# PWR_SW.net
KiCad netlist of a schematic drawn in Altium Designer
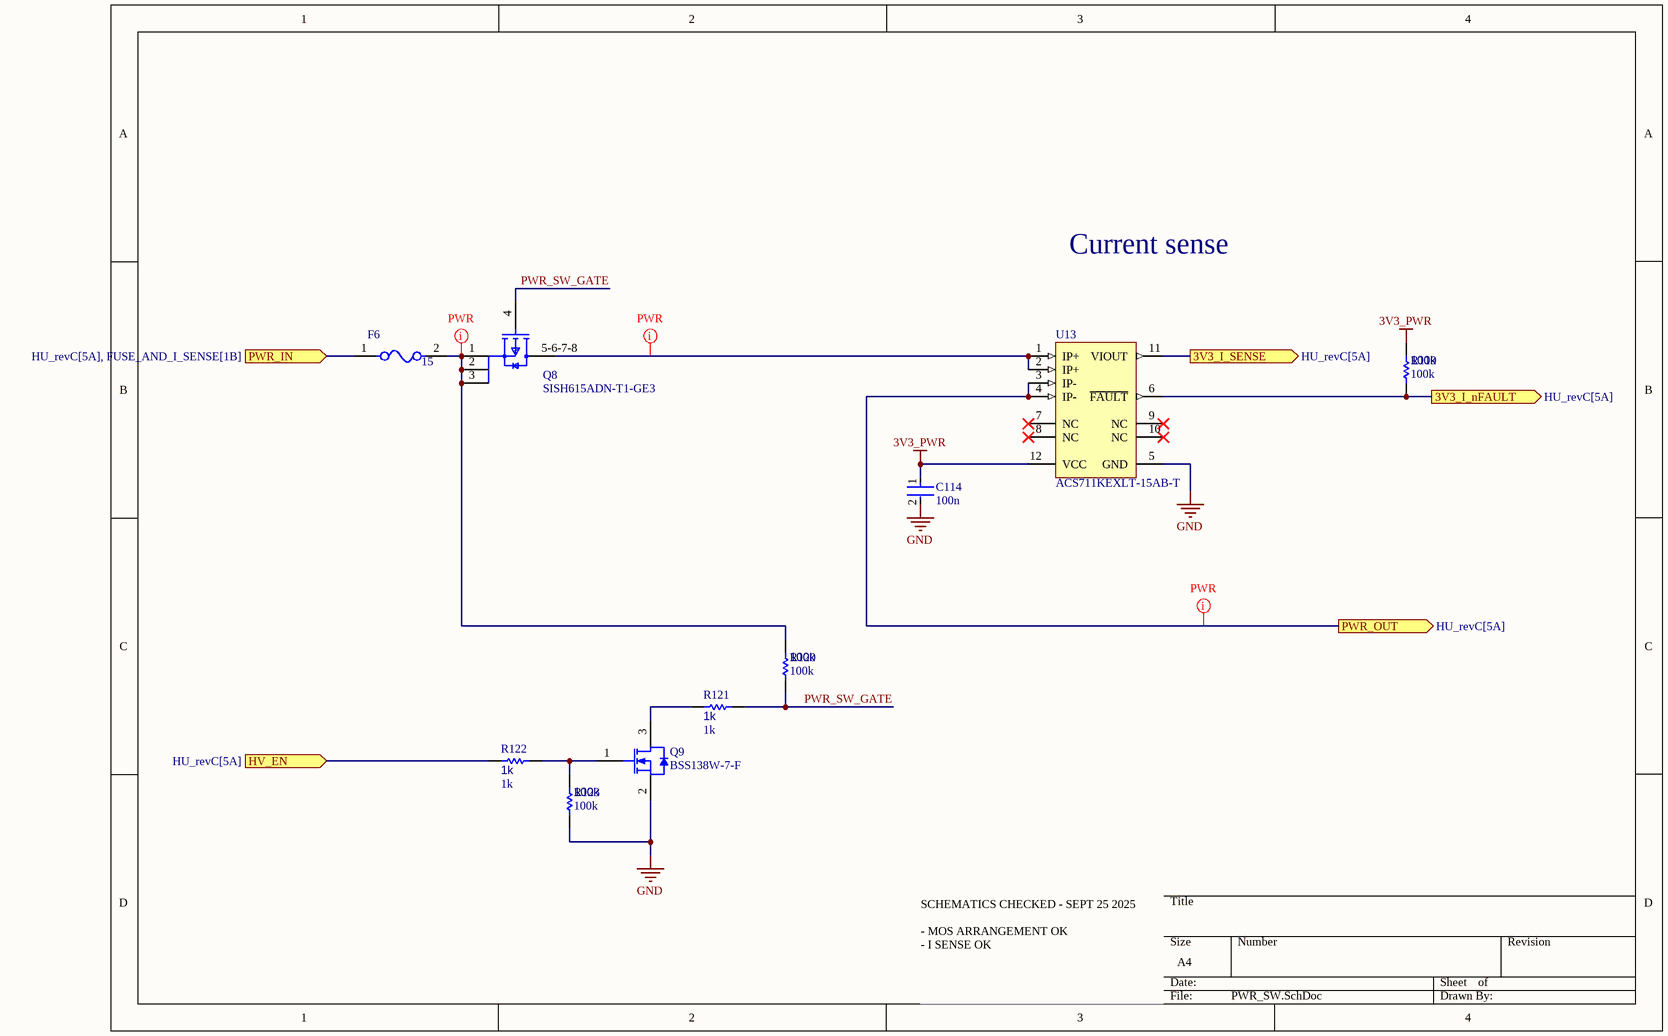
[diagram p0: PWR_SW.SchDoc]

(export (version "E")
  (design (tool "Eeschema 10.0.6"))
  (components
    (comp (ref "C114")
      (value "100n")
      (footprint "FP-0402-L_1_0_0_05-W_0_5-IPC_A")
      (description "LARGE PADS, 0402 CAP, CHANGE COMMENT TO MATCH REAL P/N")
      (libsource (lib "Space Concordia") (part "b4654b650e69147ec39a6b967a45e02"))
    )
    (comp (ref "F6")
      (value "15")
      (footprint "FP-0685T-MFG")
      (description "FUSE BOARD MNT 5A 63VAC/VDC 1206")
      (libsource (lib "Altium Content Vault") (part "5bcf9b9f640e542cf0359d10258e979"))
    )
    (comp (ref "Q8")
      (value "SISH615ADN-T1-GE3")
      (footprint "SISH615ADN-T1-GE3-Footprint-1")
      (description "Trans MOSFET P-CH 20V 22.1A 8-Pin PowerPAK 1212 EP T/R")
      (libsource (lib "Space Concordia") (part "CMP-013-00036-4"))
    )
    (comp (ref "Q9")
      (value "BSS138W-7-F")
      (footprint "DIOD-SOT323-3_V")
      (fields (field (name "MANUFACTURER") "DiodesIncorporated"))
      (libsource (lib "Altium Content Vault") (part "NEMOS-GSD-3"))
    )
    (comp (ref "R119")
      (value "100k")
      (footprint "R0603B")
      (description "Resistor")
      (fields (field (name "ALTIUM_VALUE") "100k"))
      (libsource (lib "Space Concordia") (part "Resistor"))
    )
    (comp (ref "R120")
      (value "100k")
      (footprint "R0603B")
      (description "Resistor")
      (fields (field (name "ALTIUM_VALUE") "100k"))
      (libsource (lib "Space Concordia") (part "Resistor"))
    )
    (comp (ref "R121")
      (value "1k")
      (footprint "R0603B")
      (description "Resistor")
      (fields (field (name "ALTIUM_VALUE") "1k"))
      (libsource (lib "Space Concordia") (part "Resistor"))
    )
    (comp (ref "R122")
      (value "1k")
      (footprint "R0603B")
      (description "Resistor")
      (fields (field (name "ALTIUM_VALUE") "1k"))
      (libsource (lib "Space Concordia") (part "Resistor"))
    )
    (comp (ref "R123")
      (value "100k")
      (footprint "R0603B")
      (description "Resistor")
      (fields (field (name "ALTIUM_VALUE") "100k"))
      (libsource (lib "Space Concordia") (part "Resistor"))
    )
    (comp (ref "U13")
      (value "ACS711KEXLT-15AB-T")
      (footprint "ALEG-EX-12_V")
      (libsource (lib "Altium Content Vault") (part "ALEG-ACS711-QFN-12"))
    )
  )
  (nets
    (net (code "1") (name "/3V3_I_SENSE") (class "Default")
      (node (ref "U13") (pin "11") (pinfunction "VIOUT_11") (pintype "output"))
    )
    (net (code "2") (name "/3V3_I_nFAULT") (class "Default")
      (node (ref "R119") (pin "1") (pinfunction "1_1") (pintype "passive"))
      (node (ref "U13") (pin "6") (pinfunction "~{FAULT}_6") (pintype "output"))
    )
    (net (code "3") (name "/HV_EN") (class "Default")
      (node (ref "R122") (pin "1") (pinfunction "1_1") (pintype "passive"))
    )
    (net (code "4") (name "/PWR_IN") (class "Default")
      (node (ref "F6") (pin "1") (pinfunction "1_1") (pintype "passive"))
    )
    (net (code "5") (name "/PWR_OUT") (class "Default")
      (node (ref "U13") (pin "3") (pinfunction "IP-_3") (pintype "input"))
      (node (ref "U13") (pin "4") (pinfunction "IP-_4") (pintype "input"))
    )
    (net (code "6") (name "/PWR_SW_GATE") (class "Default")
      (node (ref "Q8") (pin "4") (pinfunction "G_4") (pintype "passive"))
      (node (ref "R120") (pin "1") (pinfunction "1_1") (pintype "passive"))
      (node (ref "R121") (pin "2") (pinfunction "2_2") (pintype "passive"))
    )
    (net (code "7") (name "3V3_PWR") (class "Default")
      (node (ref "C114") (pin "1") (pinfunction "1_1") (pintype "passive"))
      (node (ref "R119") (pin "2") (pinfunction "2_2") (pintype "passive"))
      (node (ref "U13") (pin "12") (pinfunction "VCC_12") (pintype "power_in"))
    )
    (net (code "8") (name "GND") (class "Default")
      (node (ref "C114") (pin "2") (pinfunction "2_2") (pintype "passive"))
      (node (ref "Q9") (pin "2") (pinfunction "S_2") (pintype "passive"))
      (node (ref "R123") (pin "1") (pinfunction "1_1") (pintype "passive"))
      (node (ref "U13") (pin "5") (pinfunction "GND_5") (pintype "power_in"))
    )
    (net (code "9") (name "Net-(F6-Pad2)") (class "Default")
      (node (ref "F6") (pin "2") (pinfunction "2_2") (pintype "passive"))
      (node (ref "Q8") (pin "1") (pinfunction "S_1") (pintype "passive"))
      (node (ref "Q8") (pin "2") (pinfunction "S_2") (pintype "passive"))
      (node (ref "Q8") (pin "3") (pinfunction "S_3") (pintype "passive"))
      (node (ref "R120") (pin "2") (pinfunction "2_2") (pintype "passive"))
    )
    (net (code "10") (name "Net-(Q8-D)") (class "Default")
      (node (ref "Q8") (pin "5-6-7-8") (pinfunction "D_5-6-7-8") (pintype "passive"))
      (node (ref "U13") (pin "1") (pinfunction "IP+_1") (pintype "input"))
      (node (ref "U13") (pin "2") (pinfunction "IP+_2") (pintype "input"))
    )
    (net (code "11") (name "Net-(Q9-D)") (class "Default")
      (node (ref "Q9") (pin "3") (pinfunction "D_3") (pintype "passive"))
      (node (ref "R121") (pin "1") (pinfunction "1_1") (pintype "passive"))
    )
    (net (code "12") (name "Net-(Q9-G)") (class "Default")
      (node (ref "Q9") (pin "1") (pinfunction "G_1") (pintype "passive"))
      (node (ref "R122") (pin "2") (pinfunction "2_2") (pintype "passive"))
      (node (ref "R123") (pin "2") (pinfunction "2_2") (pintype "passive"))
    )
    (net (code "13") (name "unconnected-(U13-NC-Pad7)") (class "Default")
      (node (ref "U13") (pin "7") (pinfunction "NC_7") (pintype "passive+no_connect"))
    )
    (net (code "14") (name "unconnected-(U13-NC-Pad8)") (class "Default")
      (node (ref "U13") (pin "8") (pinfunction "NC_8") (pintype "passive+no_connect"))
    )
    (net (code "15") (name "unconnected-(U13-NC-Pad9)") (class "Default")
      (node (ref "U13") (pin "9") (pinfunction "NC_9") (pintype "passive+no_connect"))
    )
    (net (code "16") (name "unconnected-(U13-NC-Pad10)") (class "Default")
      (node (ref "U13") (pin "10") (pinfunction "NC_10") (pintype "passive+no_connect"))
    )
  )
)
